# IR_TEMP_SENSE.net
KiCad netlist of a schematic drawn in Altium Designer
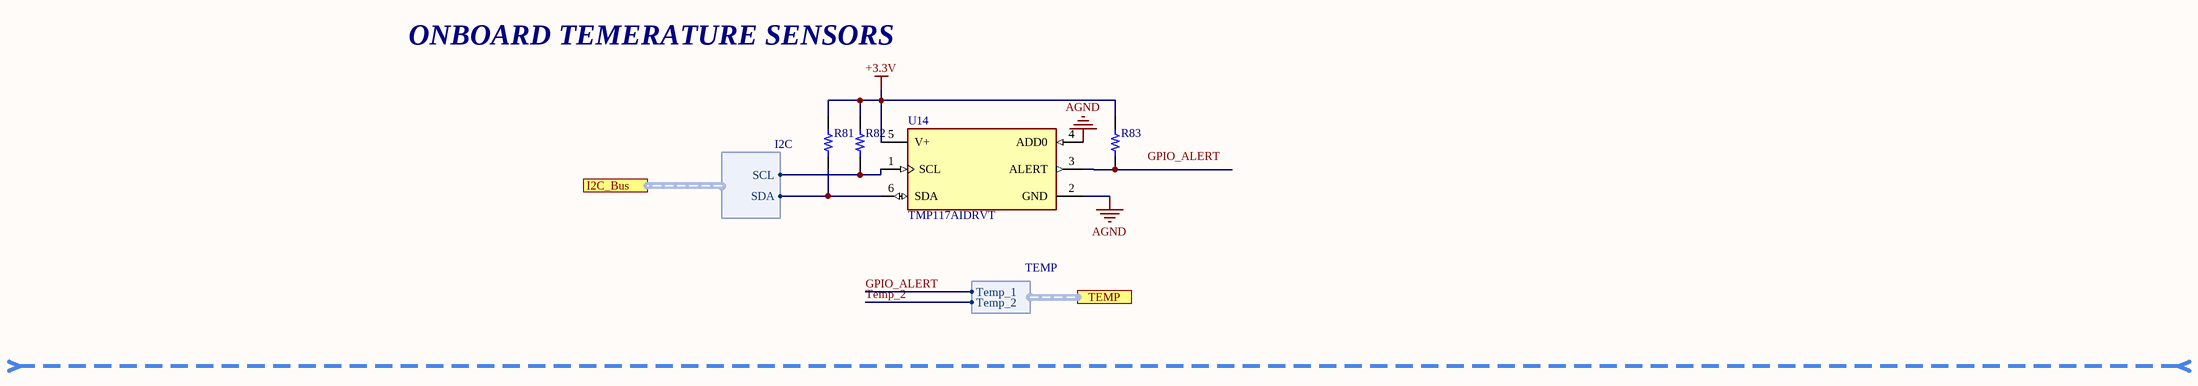
[diagram p0: IR_TEMP_SENSE.SchDoc]

(export (version "E")
  (design (tool "Eeschema 10.0.6"))
  (components
    (comp (ref "R81")
      (value "~")
      (footprint "RES 0603_1608")
      (description "RES 4.99K OHM 0.1% 1/16W 0603")
      (fields
        (field (name "PART NUMBER") "RNCS0603BKE4K99")
        (field (name "MANUFACTURER") "Stackpole Electronics Inc")
      )
      (libsource (lib "Celestial Altium Library - altium_library") (part "Resistor"))
    )
    (comp (ref "R82")
      (value "4.99 kOhms")
      (footprint "RES 0603_1608")
      (description "RES 4.99K OHM 0.1% 1/16W 0603")
      (fields
        (field (name "PART NUMBER") "RNCS0603BKE4K99")
        (field (name "MANUFACTURER") "Stackpole Electronics Inc")
      )
      (libsource (lib "Celestial Altium Library - altium_library") (part "Resistor"))
    )
    (comp (ref "R83")
      (value "4.99 kOhms")
      (footprint "RES 0603_1608")
      (description "RES 4.99K OHM 0.1% 1/16W 0603")
      (fields
        (field (name "PART NUMBER") "RNCS0603BKE4K99")
        (field (name "MANUFACTURER") "Stackpole Electronics Inc")
      )
      (libsource (lib "Celestial Altium Library - altium_library") (part "Resistor"))
    )
    (comp (ref "U14")
      (value "TMP117AIDRVT")
      (footprint "FP-DRV0006B-MFG")
      (description "SENSOR TEMP")
      (libsource (lib "Altium Content Vault") (part "9ee4a5d11dd2b01332c971eb90ce9a7"))
    )
  )
  (nets
    (net (code "3") (name "+3.3V") (class "Default")
      (node (ref "R81") (pin "2") (pinfunction "2_2") (pintype "passive"))
      (node (ref "R82") (pin "2") (pinfunction "2_2") (pintype "passive"))
      (node (ref "R83") (pin "2") (pinfunction "2_2") (pintype "passive"))
      (node (ref "U14") (pin "5") (pinfunction "V+_5") (pintype "power_in"))
    )
    (net (code "8") (name "AGND") (class "Default")
      (node (ref "U14") (pin "2") (pinfunction "GND_2") (pintype "power_in"))
      (node (ref "U14") (pin "4") (pinfunction "ADD0_4") (pintype "input"))
    )
    (net (code "9") (name "Net-(U14-ALERT)") (class "Default")
      (node (ref "R83") (pin "1") (pinfunction "1_1") (pintype "passive"))
      (node (ref "U14") (pin "3") (pinfunction "ALERT_3") (pintype "output"))
    )
    (net (code "10") (name "Net-(U14-SCL)") (class "Default")
      (node (ref "R82") (pin "1") (pinfunction "1_1") (pintype "passive"))
      (node (ref "U14") (pin "1") (pinfunction "SCL_1") (pintype "input"))
    )
    (net (code "11") (name "Net-(U14-SDA)") (class "Default")
      (node (ref "R81") (pin "1") (pinfunction "1_1") (pintype "passive"))
      (node (ref "U14") (pin "6") (pinfunction "SDA_6") (pintype "bidirectional"))
    )
  )
)
